# LEbalunfeed.net
KiCad netlist of a schematic drawn in EAGLE
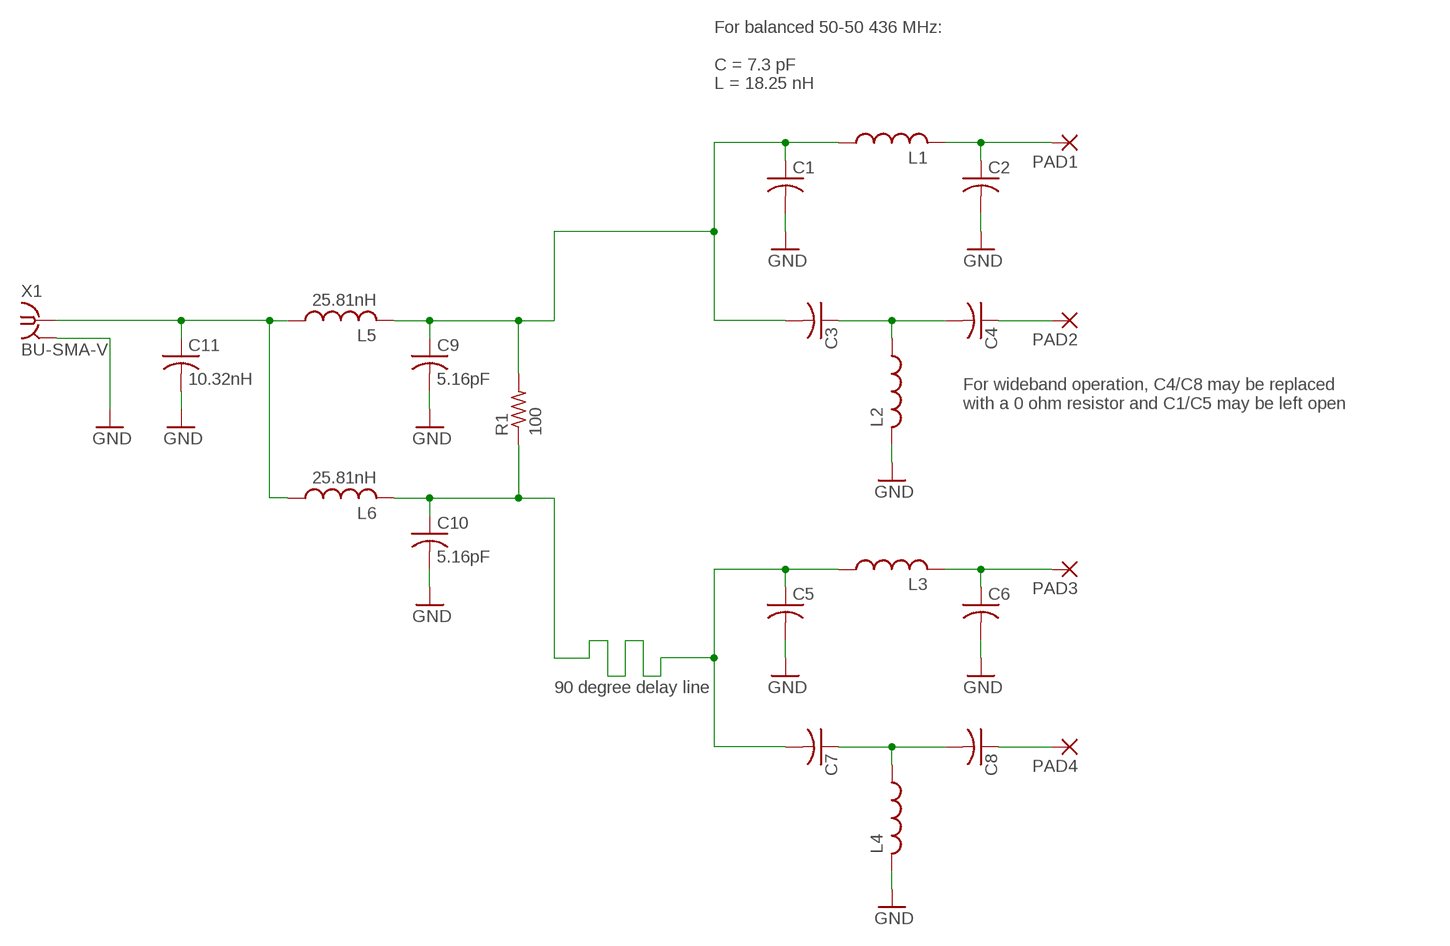
[diagram p0: schematic, sheet 1]

(export (version "E")
  (design (tool "Eeschema 10.0.6"))
  (components
    (comp (ref "C1")
      (value "C-USC1608")
      (footprint "eagle-import:C1608")
      (libsource (lib "eagle-import") (part "C-USC1608"))
    )
    (comp (ref "C2")
      (value "C-USC1608")
      (footprint "eagle-import:C1608")
      (libsource (lib "eagle-import") (part "C-USC1608"))
    )
    (comp (ref "C3")
      (value "C-USC1608")
      (footprint "eagle-import:C1608")
      (libsource (lib "eagle-import") (part "C-USC1608"))
    )
    (comp (ref "C4")
      (value "C-USC1608")
      (footprint "eagle-import:C1608")
      (libsource (lib "eagle-import") (part "C-USC1608"))
    )
    (comp (ref "C5")
      (value "C-USC1608")
      (footprint "eagle-import:C1608")
      (libsource (lib "eagle-import") (part "C-USC1608"))
    )
    (comp (ref "C6")
      (value "C-USC1608")
      (footprint "eagle-import:C1608")
      (libsource (lib "eagle-import") (part "C-USC1608"))
    )
    (comp (ref "C7")
      (value "C-USC1608")
      (footprint "eagle-import:C1608")
      (libsource (lib "eagle-import") (part "C-USC1608"))
    )
    (comp (ref "C8")
      (value "C-USC1608")
      (footprint "eagle-import:C1608")
      (libsource (lib "eagle-import") (part "C-USC1608"))
    )
    (comp (ref "C9")
      (value "5.16pF")
      (footprint "eagle-import:C1608")
      (libsource (lib "eagle-import") (part "C-USC1608"))
    )
    (comp (ref "C10")
      (value "5.16pF")
      (footprint "eagle-import:C1608")
      (libsource (lib "eagle-import") (part "C-USC1608"))
    )
    (comp (ref "C11")
      (value "10.32nH")
      (footprint "eagle-import:C1608")
      (libsource (lib "eagle-import") (part "C-USC1608"))
    )
    (comp (ref "L1")
      (value "L-USL2012C")
      (footprint "eagle-import:L2012C")
      (libsource (lib "eagle-import") (part "L-USL2012C"))
    )
    (comp (ref "L2")
      (value "L-USL2012C")
      (footprint "eagle-import:L2012C")
      (libsource (lib "eagle-import") (part "L-USL2012C"))
    )
    (comp (ref "L3")
      (value "L-USL2012C")
      (footprint "eagle-import:L2012C")
      (libsource (lib "eagle-import") (part "L-USL2012C"))
    )
    (comp (ref "L4")
      (value "L-USL2012C")
      (footprint "eagle-import:L2012C")
      (libsource (lib "eagle-import") (part "L-USL2012C"))
    )
    (comp (ref "L5")
      (value "25.81nH")
      (footprint "eagle-import:L2012C")
      (libsource (lib "eagle-import") (part "L-USL2012C"))
    )
    (comp (ref "L6")
      (value "25.81nH")
      (footprint "eagle-import:L2012C")
      (libsource (lib "eagle-import") (part "L-USL2012C"))
    )
    (comp (ref "PAD1")
      (value "0")
      (footprint "eagle-import:CMMOUNTPAD2")
      (libsource (lib "eagle-import") (part "ANTENNAPAD2"))
    )
    (comp (ref "PAD2")
      (value "180")
      (footprint "eagle-import:CMMOUNTPAD2")
      (libsource (lib "eagle-import") (part "ANTENNAPAD2"))
    )
    (comp (ref "PAD3")
      (value "90")
      (footprint "eagle-import:CMMOUNTPAD2")
      (libsource (lib "eagle-import") (part "ANTENNAPAD2"))
    )
    (comp (ref "PAD4")
      (value "270")
      (footprint "eagle-import:CMMOUNTPAD2")
      (libsource (lib "eagle-import") (part "ANTENNAPAD2"))
    )
    (comp (ref "R1")
      (value "100")
      (footprint "eagle-import:R2012")
      (libsource (lib "eagle-import") (part "R-US_R2012"))
    )
    (comp (ref "X1")
      (value "BU-SMA-V")
      (footprint "eagle-import:BU-SMA-V")
      (libsource (lib "eagle-import") (part "BU-SMA-V"))
    )
  )
  (nets
    (net (code "1") (name "GND") (class "Default")
      (node (ref "C1") (pin "2") (pinfunction "2_2") (pintype "passive"))
      (node (ref "C10") (pin "2") (pinfunction "2_2") (pintype "passive"))
      (node (ref "C11") (pin "2") (pinfunction "2_2") (pintype "passive"))
      (node (ref "C2") (pin "2") (pinfunction "2_2") (pintype "passive"))
      (node (ref "C5") (pin "2") (pinfunction "2_2") (pintype "passive"))
      (node (ref "C6") (pin "2") (pinfunction "2_2") (pintype "passive"))
      (node (ref "C9") (pin "2") (pinfunction "2_2") (pintype "passive"))
      (node (ref "L2") (pin "2") (pinfunction "2_2") (pintype "passive"))
      (node (ref "L4") (pin "2") (pinfunction "2_2") (pintype "passive"))
      (node (ref "X1") (pin "2") (pinfunction "2_2") (pintype "passive"))
      (node (ref "X1") (pin "3") (pinfunction "2_3") (pintype "passive"))
      (node (ref "X1") (pin "4") (pinfunction "2_4") (pintype "passive"))
      (node (ref "X1") (pin "5") (pinfunction "2_5") (pintype "passive"))
    )
    (net (code "2") (name "Net-(C1-Pad1)") (class "Default")
      (node (ref "C1") (pin "1") (pinfunction "1_1") (pintype "passive"))
      (node (ref "C3") (pin "2") (pinfunction "2_2") (pintype "passive"))
      (node (ref "C9") (pin "1") (pinfunction "1_1") (pintype "passive"))
      (node (ref "L1") (pin "1") (pinfunction "1_1") (pintype "passive"))
      (node (ref "L5") (pin "2") (pinfunction "2_2") (pintype "passive"))
      (node (ref "R1") (pin "2") (pinfunction "2_2") (pintype "passive"))
    )
    (net (code "3") (name "Net-(C3-Pad1)") (class "Default")
      (node (ref "C3") (pin "1") (pinfunction "1_1") (pintype "passive"))
      (node (ref "C4") (pin "2") (pinfunction "2_2") (pintype "passive"))
      (node (ref "L2") (pin "1") (pinfunction "1_1") (pintype "passive"))
    )
    (net (code "4") (name "Net-(C7-Pad1)") (class "Default")
      (node (ref "C7") (pin "1") (pinfunction "1_1") (pintype "passive"))
      (node (ref "C8") (pin "2") (pinfunction "2_2") (pintype "passive"))
      (node (ref "L4") (pin "1") (pinfunction "1_1") (pintype "passive"))
    )
    (net (code "5") (name "Net-(C10-Pad1)") (class "Default")
      (node (ref "C10") (pin "1") (pinfunction "1_1") (pintype "passive"))
      (node (ref "C5") (pin "1") (pinfunction "1_1") (pintype "passive"))
      (node (ref "C7") (pin "2") (pinfunction "2_2") (pintype "passive"))
      (node (ref "L3") (pin "1") (pinfunction "1_1") (pintype "passive"))
      (node (ref "L6") (pin "2") (pinfunction "2_2") (pintype "passive"))
      (node (ref "R1") (pin "1") (pinfunction "1_1") (pintype "passive"))
    )
    (net (code "6") (name "Net-(C11-Pad1)") (class "Default")
      (node (ref "C11") (pin "1") (pinfunction "1_1") (pintype "passive"))
      (node (ref "L5") (pin "1") (pinfunction "1_1") (pintype "passive"))
      (node (ref "L6") (pin "1") (pinfunction "1_1") (pintype "passive"))
      (node (ref "X1") (pin "1") (pinfunction "1_1") (pintype "passive"))
    )
    (net (code "7") (name "Net-(PAD1-P)") (class "Default")
      (node (ref "C2") (pin "1") (pinfunction "1_1") (pintype "passive"))
      (node (ref "L1") (pin "2") (pinfunction "2_2") (pintype "passive"))
      (node (ref "PAD1") (pin "P$1") (pinfunction "P_P$1") (pintype "passive"))
    )
    (net (code "8") (name "Net-(PAD2-P)") (class "Default")
      (node (ref "C4") (pin "1") (pinfunction "1_1") (pintype "passive"))
      (node (ref "PAD2") (pin "P$1") (pinfunction "P_P$1") (pintype "passive"))
    )
    (net (code "9") (name "Net-(PAD3-P)") (class "Default")
      (node (ref "C6") (pin "1") (pinfunction "1_1") (pintype "passive"))
      (node (ref "L3") (pin "2") (pinfunction "2_2") (pintype "passive"))
      (node (ref "PAD3") (pin "P$1") (pinfunction "P_P$1") (pintype "passive"))
    )
    (net (code "10") (name "Net-(PAD4-P)") (class "Default")
      (node (ref "C8") (pin "1") (pinfunction "1_1") (pintype "passive"))
      (node (ref "PAD4") (pin "P$1") (pinfunction "P_P$1") (pintype "passive"))
    )
  )
)
